# CSS811_BME280_Breakout.net
KiCad netlist of a schematic drawn in EAGLE
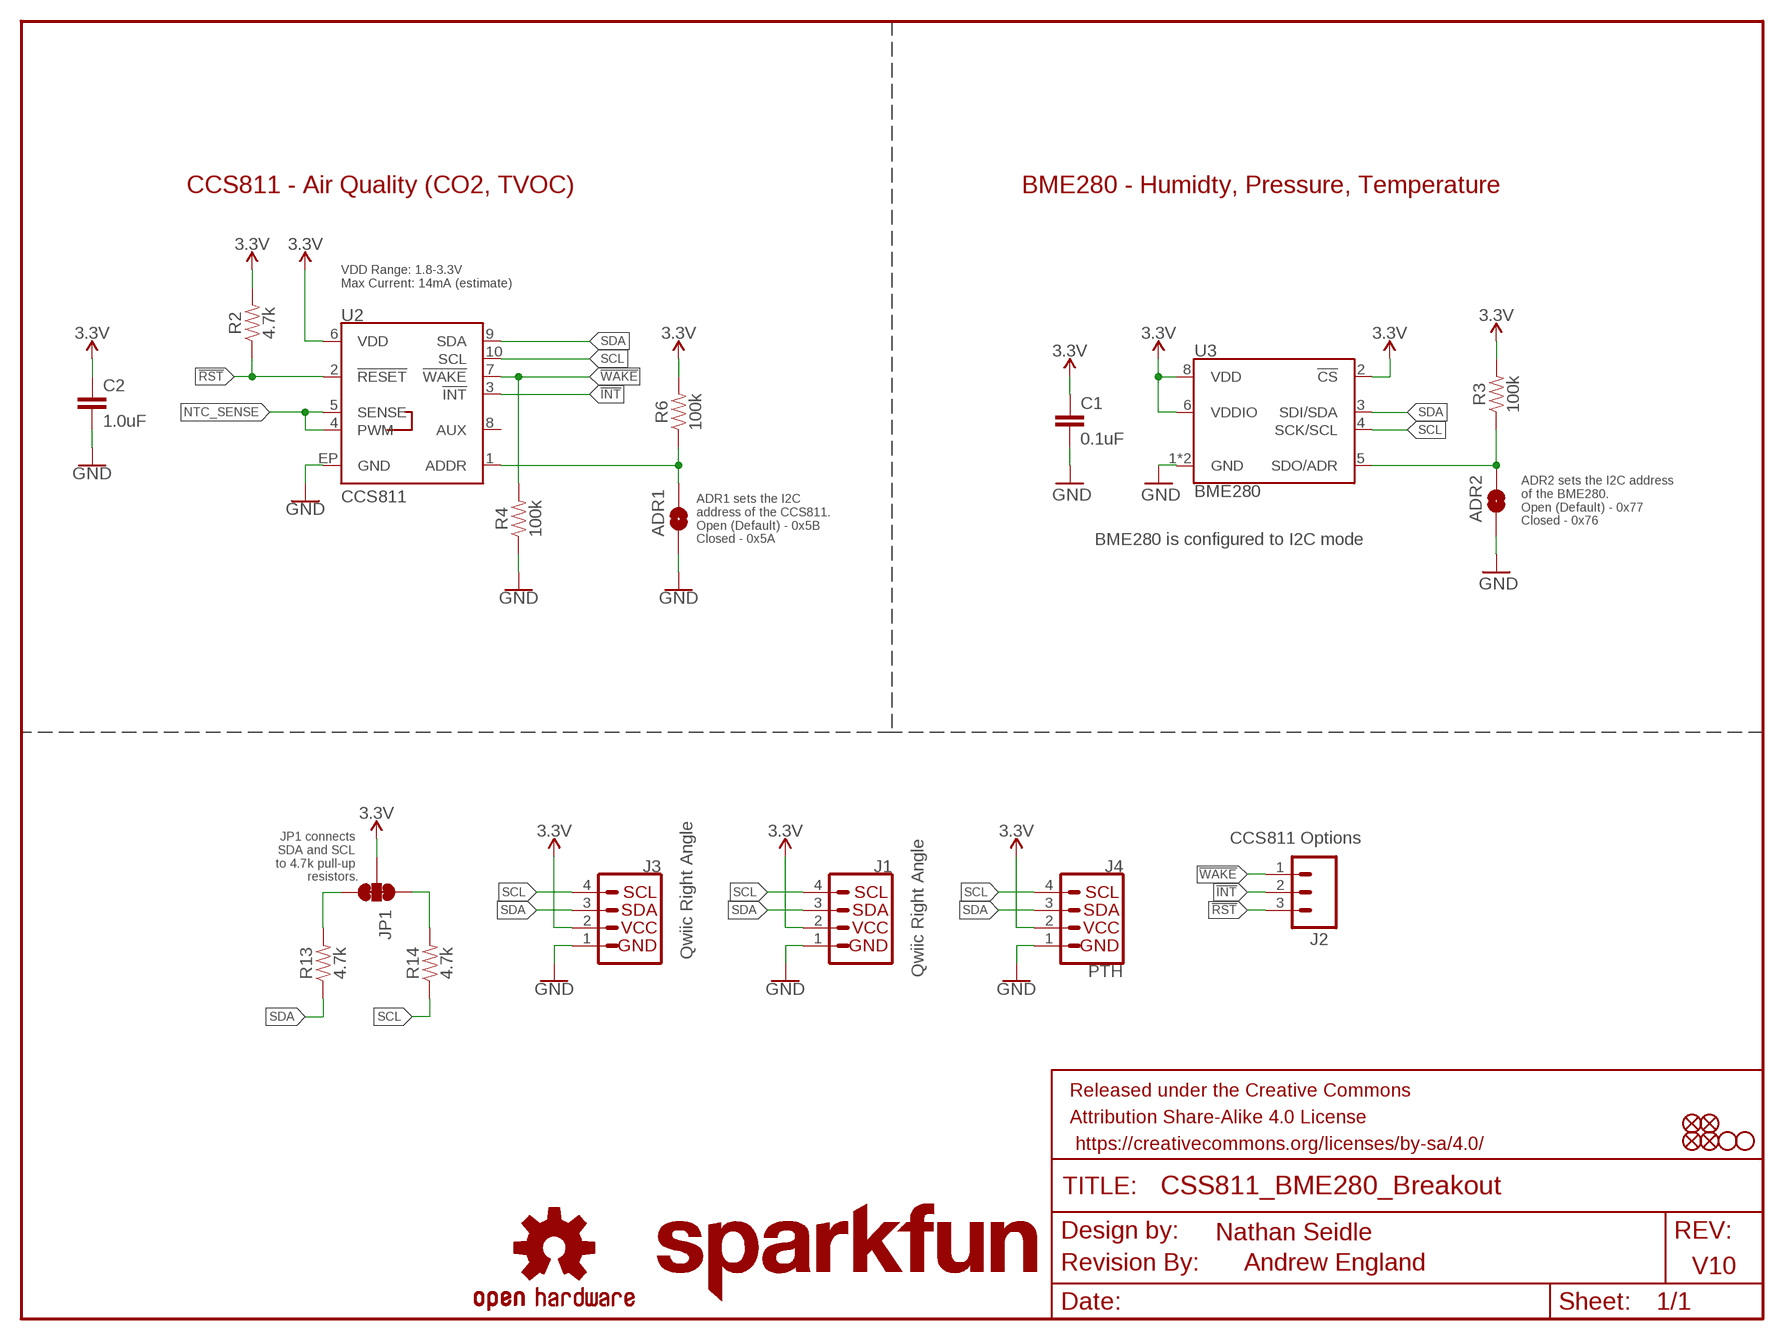
[diagram p0: schematic, sheet 1]

(export (version "E")
  (design (tool "Eeschema 10.0.6"))
  (components
    (comp (ref "ADR1")
      (value "JUMPER-SMT_2_NO_SILK")
      (footprint "eagle-import:SMT-JUMPER_2_NO_SILK")
      (libsource (lib "eagle-import") (part "JUMPER-SMT_2_NO_SILK"))
    )
    (comp (ref "ADR2")
      (value "JUMPER-SMT_2_NO_SILK")
      (footprint "eagle-import:SMT-JUMPER_2_NO_SILK")
      (libsource (lib "eagle-import") (part "JUMPER-SMT_2_NO_SILK"))
    )
    (comp (ref "C1")
      (value "0.1uF")
      (footprint "eagle-import:0603")
      (libsource (lib "eagle-import") (part "0.1UF-0603-25V-(+80/-20%)"))
    )
    (comp (ref "C2")
      (value "1.0uF")
      (footprint "eagle-import:0603")
      (libsource (lib "eagle-import") (part "1.0UF-0603-16V-10%"))
    )
    (comp (ref "FD1")
      (value "FIDUCIAL1X2")
      (footprint "eagle-import:FIDUCIAL-1X2")
      (libsource (lib "eagle-import") (part "FIDUCIAL1X2"))
    )
    (comp (ref "FD2")
      (value "FIDUCIAL1X2")
      (footprint "eagle-import:FIDUCIAL-1X2")
      (libsource (lib "eagle-import") (part "FIDUCIAL1X2"))
    )
    (comp (ref "FD3")
      (value "FIDUCIAL1X2")
      (footprint "eagle-import:FIDUCIAL-1X2")
      (libsource (lib "eagle-import") (part "FIDUCIAL1X2"))
    )
    (comp (ref "FD4")
      (value "FIDUCIAL1X2")
      (footprint "eagle-import:FIDUCIAL-1X2")
      (libsource (lib "eagle-import") (part "FIDUCIAL1X2"))
    )
    (comp (ref "FRAME1")
      (value "FRAME-LETTER")
      (footprint "eagle-import:CREATIVE_COMMONS")
      (libsource (lib "eagle-import") (part "FRAME-LETTER"))
    )
    (comp (ref "H2")
      (value "STAND-OFF")
      (footprint "eagle-import:STAND-OFF")
      (libsource (lib "eagle-import") (part "STAND-OFF"))
    )
    (comp (ref "H4")
      (value "STAND-OFF")
      (footprint "eagle-import:STAND-OFF")
      (libsource (lib "eagle-import") (part "STAND-OFF"))
    )
    (comp (ref "J1")
      (value "Qwiic Right Angle")
      (footprint "eagle-import:1X04_1MM_RA")
      (libsource (lib "eagle-import") (part "I2C_STANDARDQWIIC"))
    )
    (comp (ref "J2")
      (value "CCS811 Options")
      (footprint "eagle-import:1X03_NO_SILK")
      (libsource (lib "eagle-import") (part "CONN_031X03_NO_SILK"))
    )
    (comp (ref "J3")
      (value "Qwiic Right Angle")
      (footprint "eagle-import:1X04_1MM_RA")
      (libsource (lib "eagle-import") (part "I2C_STANDARDQWIIC"))
    )
    (comp (ref "J4")
      (value "PTH")
      (footprint "eagle-import:1X04_NO_SILK")
      (libsource (lib "eagle-import") (part "SparkX_I2C_STANDARD_NO_SILK"))
    )
    (comp (ref "JP1")
      (value "JUMPER-SMT_3_2-NC_TRACE_SILK")
      (footprint "eagle-import:SMT-JUMPER_3_2-NC_TRACE_SILK")
      (libsource (lib "eagle-import") (part "JUMPER-SMT_3_2-NC_TRACE_SILK"))
    )
    (comp (ref "LOGO1")
      (value "SFE_LOGO_NAME.1_INCH")
      (footprint "eagle-import:SFE_LOGO_NAME_.1")
      (libsource (lib "eagle-import") (part "SFE_LOGO_NAME.1_INCH"))
    )
    (comp (ref "LOGO2")
      (value "REVISION")
      (footprint "eagle-import:REVISION")
      (libsource (lib "eagle-import") (part "REVISION"))
    )
    (comp (ref "LOGO4")
      (value "OSHW-LOGOS")
      (footprint "eagle-import:OSHW-LOGO-S")
      (libsource (lib "eagle-import") (part "OSHW-LOGOS"))
    )
    (comp (ref "R2")
      (value "4.7k")
      (footprint "eagle-import:0603")
      (libsource (lib "eagle-import") (part "4.7KOHM-0603-1/10W-1%"))
    )
    (comp (ref "R3")
      (value "100k")
      (footprint "eagle-import:0603")
      (libsource (lib "eagle-import") (part "100KOHM-0603-1/10W-1%"))
    )
    (comp (ref "R4")
      (value "100k")
      (footprint "eagle-import:0603")
      (libsource (lib "eagle-import") (part "100KOHM-0603-1/10W-1%"))
    )
    (comp (ref "R6")
      (value "100k")
      (footprint "eagle-import:0603")
      (libsource (lib "eagle-import") (part "100KOHM-0603-1/10W-1%"))
    )
    (comp (ref "R13")
      (value "4.7k")
      (footprint "eagle-import:0603")
      (libsource (lib "eagle-import") (part "4.7KOHM-0603-1/10W-1%"))
    )
    (comp (ref "R14")
      (value "4.7k")
      (footprint "eagle-import:0603")
      (libsource (lib "eagle-import") (part "4.7KOHM-0603-1/10W-1%"))
    )
    (comp (ref "U2")
      (value "CCS811")
      (footprint "eagle-import:LGA10")
      (libsource (lib "eagle-import") (part "CCS811PRODUCTION"))
    )
    (comp (ref "U3")
      (value "BME280")
      (footprint "eagle-import:LGA-8-2.5X2.5")
      (libsource (lib "eagle-import") (part "BME280"))
    )
  )
  (nets
    (net (code "1") (name "/~{INT}") (class "Default")
      (node (ref "J2") (pin "2") (pinfunction "2_2") (pintype "passive"))
      (node (ref "U2") (pin "3") (pinfunction "~{INT}_3") (pintype "bidirectional"))
    )
    (net (code "2") (name "/~{RST}") (class "Default")
      (node (ref "J2") (pin "3") (pinfunction "3_3") (pintype "passive"))
      (node (ref "R2") (pin "1") (pinfunction "1_1") (pintype "passive"))
      (node (ref "U2") (pin "2") (pinfunction "~{RESET}_2") (pintype "bidirectional"))
    )
    (net (code "3") (name "/~{WAKE}") (class "Default")
      (node (ref "J2") (pin "1") (pinfunction "1_1") (pintype "passive"))
      (node (ref "R4") (pin "2") (pinfunction "2_2") (pintype "passive"))
      (node (ref "U2") (pin "7") (pinfunction "~{WAKE}_7") (pintype "bidirectional"))
    )
    (net (code "4") (name "3.3V") (class "Default")
      (node (ref "C1") (pin "1") (pinfunction "1_1") (pintype "passive"))
      (node (ref "C2") (pin "1") (pinfunction "1_1") (pintype "passive"))
      (node (ref "J1") (pin "2") (pinfunction "2_2") (pintype "power_in"))
      (node (ref "J3") (pin "2") (pinfunction "2_2") (pintype "power_in"))
      (node (ref "J4") (pin "2") (pinfunction "VCC_2") (pintype "power_in"))
      (node (ref "JP1") (pin "2") (pinfunction "2_2") (pintype "passive"))
      (node (ref "R2") (pin "2") (pinfunction "2_2") (pintype "passive"))
      (node (ref "R3") (pin "2") (pinfunction "2_2") (pintype "passive"))
      (node (ref "R6") (pin "2") (pinfunction "2_2") (pintype "passive"))
      (node (ref "U2") (pin "6") (pinfunction "VDD_6") (pintype "bidirectional"))
      (node (ref "U3") (pin "2") (pinfunction "~{CS}_2") (pintype "bidirectional"))
      (node (ref "U3") (pin "6") (pinfunction "VDDIO_6") (pintype "bidirectional"))
      (node (ref "U3") (pin "8") (pinfunction "VDD_8") (pintype "bidirectional"))
    )
    (net (code "5") (name "GND") (class "Default")
      (node (ref "ADR1") (pin "1") (pinfunction "1_1") (pintype "passive"))
      (node (ref "ADR2") (pin "1") (pinfunction "1_1") (pintype "passive"))
      (node (ref "C1") (pin "2") (pinfunction "2_2") (pintype "passive"))
      (node (ref "C2") (pin "2") (pinfunction "2_2") (pintype "passive"))
      (node (ref "J1") (pin "1") (pinfunction "1_1") (pintype "power_in"))
      (node (ref "J3") (pin "1") (pinfunction "1_1") (pintype "power_in"))
      (node (ref "J4") (pin "1") (pinfunction "GND_1") (pintype "power_in"))
      (node (ref "R4") (pin "1") (pinfunction "1_1") (pintype "passive"))
      (node (ref "U2") (pin "EP") (pinfunction "GND_EP") (pintype "bidirectional"))
      (node (ref "U3") (pin "1") (pinfunction "GND_1") (pintype "bidirectional"))
      (node (ref "U3") (pin "7") (pinfunction "GND_7") (pintype "bidirectional"))
    )
    (net (code "6") (name "NTC_SENSE") (class "Default")
      (node (ref "U2") (pin "4") (pinfunction "PWM_4") (pintype "bidirectional"))
      (node (ref "U2") (pin "5") (pinfunction "SENSE_5") (pintype "bidirectional"))
    )
    (net (code "7") (name "Net-(JP1-Pad1)") (class "Default")
      (node (ref "JP1") (pin "1") (pinfunction "1_1") (pintype "passive"))
      (node (ref "R14") (pin "2") (pinfunction "2_2") (pintype "passive"))
    )
    (net (code "8") (name "Net-(JP1-Pad3)") (class "Default")
      (node (ref "JP1") (pin "3") (pinfunction "3_3") (pintype "passive"))
      (node (ref "R13") (pin "2") (pinfunction "2_2") (pintype "passive"))
    )
    (net (code "9") (name "Net-(U2-ADDR)") (class "Default")
      (node (ref "ADR1") (pin "2") (pinfunction "2_2") (pintype "passive"))
      (node (ref "R6") (pin "1") (pinfunction "1_1") (pintype "passive"))
      (node (ref "U2") (pin "1") (pinfunction "ADDR_1") (pintype "bidirectional"))
    )
    (net (code "10") (name "Net-(U3-SDO{slash}ADR)") (class "Default")
      (node (ref "ADR2") (pin "2") (pinfunction "2_2") (pintype "passive"))
      (node (ref "R3") (pin "1") (pinfunction "1_1") (pintype "passive"))
      (node (ref "U3") (pin "5") (pinfunction "SDO/ADR_5") (pintype "bidirectional"))
    )
    (net (code "11") (name "SCL") (class "Default")
      (node (ref "J1") (pin "4") (pinfunction "4_4") (pintype "passive"))
      (node (ref "J3") (pin "4") (pinfunction "4_4") (pintype "passive"))
      (node (ref "J4") (pin "4") (pinfunction "SCL_4") (pintype "passive"))
      (node (ref "R14") (pin "1") (pinfunction "1_1") (pintype "passive"))
      (node (ref "U2") (pin "10") (pinfunction "SCL_10") (pintype "bidirectional"))
      (node (ref "U3") (pin "4") (pinfunction "SCK/SCL_4") (pintype "bidirectional"))
    )
    (net (code "12") (name "SDA") (class "Default")
      (node (ref "J1") (pin "3") (pinfunction "3_3") (pintype "passive"))
      (node (ref "J3") (pin "3") (pinfunction "3_3") (pintype "passive"))
      (node (ref "J4") (pin "3") (pinfunction "SDA_3") (pintype "passive"))
      (node (ref "R13") (pin "1") (pinfunction "1_1") (pintype "passive"))
      (node (ref "U2") (pin "9") (pinfunction "SDA_9") (pintype "bidirectional"))
      (node (ref "U3") (pin "3") (pinfunction "SDI/SDA_3") (pintype "bidirectional"))
    )
    (net (code "13") (name "unconnected-(U2-AUX-Pad8)") (class "Default")
      (node (ref "U2") (pin "8") (pinfunction "AUX_8") (pintype "bidirectional"))
    )
  )
)
